# Audio.net
KiCad netlist of a schematic drawn in Altium Designer
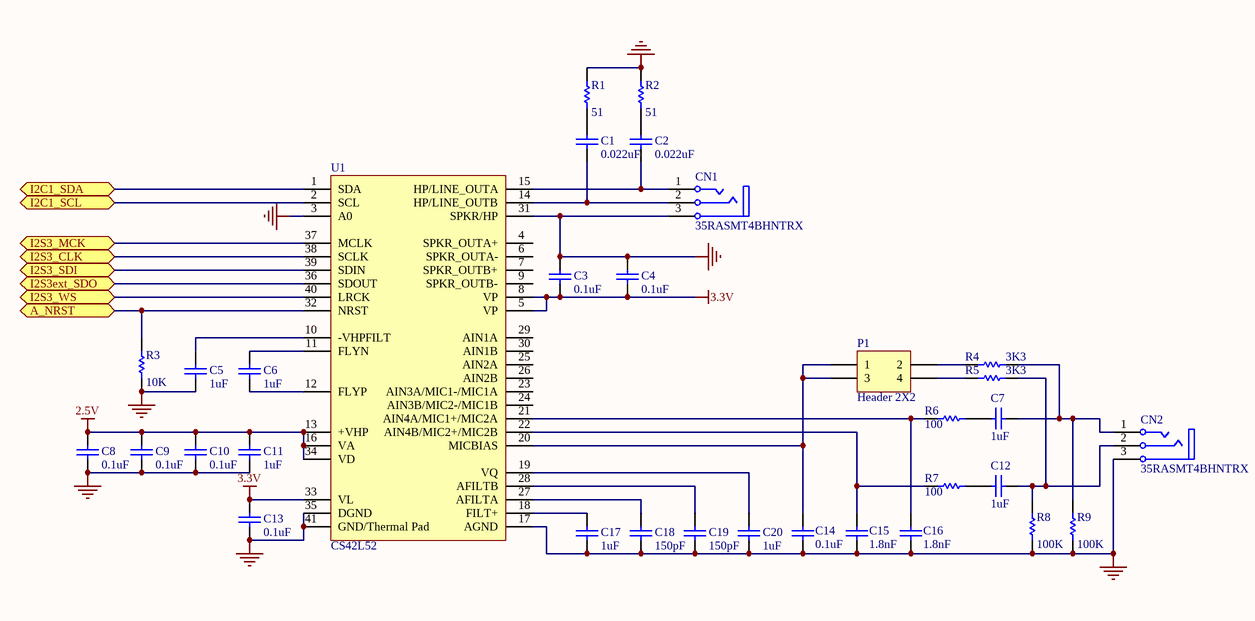
[diagram p0: Audio.SchDoc]

(export (version "E")
  (design (tool "Eeschema 10.0.6"))
  (components
    (comp (ref "C1")
      (value "0.022uF")
      (footprint "CAPC2012N")
      (description "Capacitor")
      (fields (field (name "Comment") "Cap"))
      (libsource (lib "Core429IBaseBoard") (part "Cap"))
    )
    (comp (ref "C2")
      (value "0.022uF")
      (footprint "CAPC2012N")
      (description "Capacitor")
      (fields (field (name "Comment") "Cap"))
      (libsource (lib "Core429IBaseBoard") (part "Cap"))
    )
    (comp (ref "C3")
      (value "0.1uF")
      (footprint "CAPC2012N")
      (description "Capacitor")
      (fields (field (name "Comment") "Cap"))
      (libsource (lib "Core429IBaseBoard") (part "Cap"))
    )
    (comp (ref "C4")
      (value "0.1uF")
      (footprint "CAPC2012N")
      (description "Capacitor")
      (fields (field (name "Comment") "Cap"))
      (libsource (lib "Core429IBaseBoard") (part "Cap"))
    )
    (comp (ref "C5")
      (value "1uF")
      (footprint "CAPC3216N")
      (description "Capacitor")
      (fields (field (name "Comment") "Cap"))
      (libsource (lib "Core429IBaseBoard") (part "Cap"))
    )
    (comp (ref "C6")
      (value "1uF")
      (footprint "CAPC3216N")
      (description "Capacitor")
      (fields (field (name "Comment") "Cap"))
      (libsource (lib "Core429IBaseBoard") (part "Cap"))
    )
    (comp (ref "C7")
      (value "1uF")
      (footprint "CAPC3216N")
      (description "Capacitor")
      (fields (field (name "Comment") "Cap"))
      (libsource (lib "Core429IBaseBoard") (part "Cap"))
    )
    (comp (ref "C8")
      (value "0.1uF")
      (footprint "CAPC2012N")
      (description "Capacitor")
      (fields (field (name "Comment") "Cap"))
      (libsource (lib "Core429IBaseBoard") (part "Cap"))
    )
    (comp (ref "C9")
      (value "0.1uF")
      (footprint "CAPC2012N")
      (description "Capacitor")
      (fields (field (name "Comment") "Cap"))
      (libsource (lib "Core429IBaseBoard") (part "Cap"))
    )
    (comp (ref "C10")
      (value "0.1uF")
      (footprint "CAPC2012N")
      (description "Capacitor")
      (fields (field (name "Comment") "Cap"))
      (libsource (lib "Core429IBaseBoard") (part "Cap"))
    )
    (comp (ref "C11")
      (value "1uF")
      (footprint "CAPC3216N")
      (description "Capacitor")
      (fields (field (name "Comment") "Cap"))
      (libsource (lib "Core429IBaseBoard") (part "Cap"))
    )
    (comp (ref "C12")
      (value "1uF")
      (footprint "CAPC3216N")
      (description "Capacitor")
      (fields (field (name "Comment") "Cap"))
      (libsource (lib "Core429IBaseBoard") (part "Cap"))
    )
    (comp (ref "C13")
      (value "0.1uF")
      (footprint "CAPC2012N")
      (description "Capacitor")
      (fields (field (name "Comment") "Cap"))
      (libsource (lib "Core429IBaseBoard") (part "Cap"))
    )
    (comp (ref "C14")
      (value "0.1uF")
      (footprint "CAPC2012N")
      (description "Capacitor")
      (fields (field (name "Comment") "Cap"))
      (libsource (lib "Core429IBaseBoard") (part "Cap"))
    )
    (comp (ref "C15")
      (value "1.8nF")
      (footprint "CAPC2012N")
      (description "Capacitor")
      (fields (field (name "Comment") "Cap"))
      (libsource (lib "Core429IBaseBoard") (part "Cap"))
    )
    (comp (ref "C16")
      (value "1.8nF")
      (footprint "CAPC2012N")
      (description "Capacitor")
      (fields (field (name "Comment") "Cap"))
      (libsource (lib "Core429IBaseBoard") (part "Cap"))
    )
    (comp (ref "C17")
      (value "1uF")
      (footprint "CAPC3216N")
      (description "Capacitor")
      (fields (field (name "Comment") "Cap"))
      (libsource (lib "Core429IBaseBoard") (part "Cap"))
    )
    (comp (ref "C18")
      (value "150pF")
      (footprint "CAPC2012N")
      (description "Capacitor")
      (fields (field (name "Comment") "Cap"))
      (libsource (lib "Core429IBaseBoard") (part "Cap"))
    )
    (comp (ref "C19")
      (value "150pF")
      (footprint "CAPC2012N")
      (description "Capacitor")
      (fields (field (name "Comment") "Cap"))
      (libsource (lib "Core429IBaseBoard") (part "Cap"))
    )
    (comp (ref "C20")
      (value "1uF")
      (footprint "CAPC3216N")
      (description "Capacitor")
      (fields (field (name "Comment") "Cap"))
      (libsource (lib "Core429IBaseBoard") (part "Cap"))
    )
    (comp (ref "CN1")
      (value "35RASMT4BHNTRX")
      (footprint "35RASMT4BHNTRX")
      (description "3.5mm Stereo Jack")
      (libsource (lib "Core429IBaseBoardVerE") (part "Phonejack3"))
    )
    (comp (ref "CN2")
      (value "35RASMT4BHNTRX")
      (footprint "35RASMT4BHNTRX")
      (description "3.5mm Stereo Jack")
      (libsource (lib "Core429IBaseBoardVerE") (part "Phonejack3"))
    )
    (comp (ref "P1")
      (value "Header 2X2")
      (footprint "HDR2X2")
      (description "Header, 2-Pin, Dual row")
      (libsource (lib "Core429IBaseBoardVerE") (part "Header 2X2"))
    )
    (comp (ref "R1")
      (value "51")
      (footprint "RESC2012N")
      (description "Resistor")
      (fields (field (name "Comment") "1206"))
      (libsource (lib "Core429IBaseBoard") (part "Res"))
    )
    (comp (ref "R2")
      (value "51")
      (footprint "RESC2012N")
      (description "Resistor")
      (fields (field (name "Comment") "1206"))
      (libsource (lib "Core429IBaseBoard") (part "Res"))
    )
    (comp (ref "R3")
      (value "10K")
      (footprint "RESC2012N")
      (description "Resistor")
      (fields (field (name "Comment") "1206"))
      (libsource (lib "Core429IBaseBoard") (part "Res"))
    )
    (comp (ref "R4")
      (value "3K3")
      (footprint "RESC2012N")
      (description "Resistor")
      (fields (field (name "Comment") "1206"))
      (libsource (lib "Core429IBaseBoard") (part "Res"))
    )
    (comp (ref "R5")
      (value "3K3")
      (footprint "RESC2012N")
      (description "Resistor")
      (fields (field (name "Comment") "1206"))
      (libsource (lib "Core429IBaseBoard") (part "Res"))
    )
    (comp (ref "R6")
      (value "100")
      (footprint "RESC2012N")
      (description "Resistor")
      (fields (field (name "Comment") "1206"))
      (libsource (lib "Core429IBaseBoard") (part "Res"))
    )
    (comp (ref "R7")
      (value "100")
      (footprint "RESC2012N")
      (description "Resistor")
      (fields (field (name "Comment") "1206"))
      (libsource (lib "Core429IBaseBoard") (part "Res"))
    )
    (comp (ref "R8")
      (value "100K")
      (footprint "RESC2012N")
      (description "Resistor")
      (fields (field (name "Comment") "1206"))
      (libsource (lib "Core429IBaseBoard") (part "Res"))
    )
    (comp (ref "R9")
      (value "100K")
      (footprint "RESC2012N")
      (description "Resistor")
      (fields (field (name "Comment") "1206"))
      (libsource (lib "Core429IBaseBoard") (part "Res"))
    )
    (comp (ref "U1")
      (value "CS42L52")
      (footprint "QFN50P600X600X100-40M")
      (description "Low-power, Stereo CODEC w/ Headphone & Speaker Amps")
      (libsource (lib "Core429IBaseBoardVerE") (part "CS42L52"))
    )
  )
  (nets
    (net (code "1") (name "/A_NRST") (class "Default")
      (node (ref "R3") (pin "2") (pinfunction "2_2") (pintype "passive"))
      (node (ref "U1") (pin "32") (pinfunction "NRST_32") (pintype "passive"))
    )
    (net (code "2") (name "/I2C1_SCL") (class "Default")
      (node (ref "U1") (pin "2") (pinfunction "SCL_2") (pintype "passive"))
    )
    (net (code "3") (name "/I2C1_SDA") (class "Default")
      (node (ref "U1") (pin "1") (pinfunction "SDA_1") (pintype "passive"))
    )
    (net (code "4") (name "/I2S3_CLK") (class "Default")
      (node (ref "U1") (pin "38") (pinfunction "SCLK_38") (pintype "passive"))
    )
    (net (code "5") (name "/I2S3_MCK") (class "Default")
      (node (ref "U1") (pin "37") (pinfunction "MCLK_37") (pintype "passive"))
    )
    (net (code "6") (name "/I2S3_SDI") (class "Default")
      (node (ref "U1") (pin "39") (pinfunction "SDIN_39") (pintype "passive"))
    )
    (net (code "7") (name "/I2S3_WS") (class "Default")
      (node (ref "U1") (pin "40") (pinfunction "LRCK_40") (pintype "passive"))
    )
    (net (code "8") (name "/I2S3ext_SDO") (class "Default")
      (node (ref "U1") (pin "36") (pinfunction "SDOUT_36") (pintype "passive"))
    )
    (net (code "9") (name "2.5V") (class "Default")
      (node (ref "C10") (pin "2") (pinfunction "2_2") (pintype "passive"))
      (node (ref "C11") (pin "2") (pinfunction "2_2") (pintype "passive"))
      (node (ref "C8") (pin "2") (pinfunction "2_2") (pintype "passive"))
      (node (ref "C9") (pin "2") (pinfunction "2_2") (pintype "passive"))
      (node (ref "U1") (pin "13") (pinfunction "+VHP_13") (pintype "passive"))
      (node (ref "U1") (pin "16") (pinfunction "VA_16") (pintype "passive"))
      (node (ref "U1") (pin "34") (pinfunction "VD_34") (pintype "passive"))
    )
    (net (code "10") (name "3.3V") (class "Default")
      (node (ref "C13") (pin "2") (pinfunction "2_2") (pintype "passive"))
      (node (ref "C3") (pin "1") (pinfunction "1_1") (pintype "passive"))
      (node (ref "C4") (pin "1") (pinfunction "1_1") (pintype "passive"))
      (node (ref "U1") (pin "33") (pinfunction "VL_33") (pintype "passive"))
      (node (ref "U1") (pin "5") (pinfunction "VP_5") (pintype "passive"))
      (node (ref "U1") (pin "8") (pinfunction "VP_8") (pintype "passive"))
    )
    (net (code "11") (name "DGND") (class "Default")
      (node (ref "C10") (pin "1") (pinfunction "1_1") (pintype "passive"))
      (node (ref "C11") (pin "1") (pinfunction "1_1") (pintype "passive"))
      (node (ref "C13") (pin "1") (pinfunction "1_1") (pintype "passive"))
      (node (ref "C14") (pin "2") (pinfunction "2_2") (pintype "passive"))
      (node (ref "C15") (pin "2") (pinfunction "2_2") (pintype "passive"))
      (node (ref "C16") (pin "2") (pinfunction "2_2") (pintype "passive"))
      (node (ref "C17") (pin "1") (pinfunction "1_1") (pintype "passive"))
      (node (ref "C18") (pin "1") (pinfunction "1_1") (pintype "passive"))
      (node (ref "C19") (pin "1") (pinfunction "1_1") (pintype "passive"))
      (node (ref "C20") (pin "1") (pinfunction "1_1") (pintype "passive"))
      (node (ref "C3") (pin "2") (pinfunction "2_2") (pintype "passive"))
      (node (ref "C4") (pin "2") (pinfunction "2_2") (pintype "passive"))
      (node (ref "C5") (pin "1") (pinfunction "1_1") (pintype "passive"))
      (node (ref "C8") (pin "1") (pinfunction "1_1") (pintype "passive"))
      (node (ref "C9") (pin "1") (pinfunction "1_1") (pintype "passive"))
      (node (ref "CN1") (pin "3") (pinfunction "S_3") (pintype "passive"))
      (node (ref "CN2") (pin "3") (pinfunction "S_3") (pintype "passive"))
      (node (ref "R1") (pin "2") (pinfunction "2_2") (pintype "passive"))
      (node (ref "R2") (pin "2") (pinfunction "2_2") (pintype "passive"))
      (node (ref "R3") (pin "1") (pinfunction "1_1") (pintype "passive"))
      (node (ref "R8") (pin "1") (pinfunction "1_1") (pintype "passive"))
      (node (ref "R9") (pin "1") (pinfunction "1_1") (pintype "passive"))
      (node (ref "U1") (pin "17") (pinfunction "AGND_17") (pintype "passive"))
      (node (ref "U1") (pin "3") (pinfunction "A0_3") (pintype "passive"))
      (node (ref "U1") (pin "31") (pinfunction "SPKR/HP_31") (pintype "passive"))
      (node (ref "U1") (pin "35") (pinfunction "DGND_35") (pintype "passive"))
      (node (ref "U1") (pin "41") (pinfunction "GND/Thermal_Pad_41") (pintype "passive"))
    )
    (net (code "12") (name "Net-(C1-Pad2)") (class "Default")
      (node (ref "C1") (pin "2") (pinfunction "2_2") (pintype "passive"))
      (node (ref "R1") (pin "1") (pinfunction "1_1") (pintype "passive"))
    )
    (net (code "13") (name "Net-(C2-Pad2)") (class "Default")
      (node (ref "C2") (pin "2") (pinfunction "2_2") (pintype "passive"))
      (node (ref "R2") (pin "1") (pinfunction "1_1") (pintype "passive"))
    )
    (net (code "14") (name "Net-(C7-Pad2)") (class "Default")
      (node (ref "C7") (pin "2") (pinfunction "2_2") (pintype "passive"))
      (node (ref "R6") (pin "1") (pinfunction "1_1") (pintype "passive"))
    )
    (net (code "15") (name "Net-(C12-Pad2)") (class "Default")
      (node (ref "C12") (pin "2") (pinfunction "2_2") (pintype "passive"))
      (node (ref "R7") (pin "1") (pinfunction "1_1") (pintype "passive"))
    )
    (net (code "16") (name "Net-(CN1-R)") (class "Default")
      (node (ref "C1") (pin "1") (pinfunction "1_1") (pintype "passive"))
      (node (ref "CN1") (pin "2") (pinfunction "R_2") (pintype "passive"))
      (node (ref "U1") (pin "14") (pinfunction "HP/LINE_OUTB_14") (pintype "passive"))
    )
    (net (code "17") (name "Net-(CN1-T)") (class "Default")
      (node (ref "C2") (pin "1") (pinfunction "1_1") (pintype "passive"))
      (node (ref "CN1") (pin "1") (pinfunction "T_1") (pintype "passive"))
      (node (ref "U1") (pin "15") (pinfunction "HP/LINE_OUTA_15") (pintype "passive"))
    )
    (net (code "18") (name "Net-(CN2-R)") (class "Default")
      (node (ref "C12") (pin "1") (pinfunction "1_1") (pintype "passive"))
      (node (ref "CN2") (pin "2") (pinfunction "R_2") (pintype "passive"))
      (node (ref "R5") (pin "1") (pinfunction "1_1") (pintype "passive"))
      (node (ref "R8") (pin "2") (pinfunction "2_2") (pintype "passive"))
    )
    (net (code "19") (name "Net-(CN2-T)") (class "Default")
      (node (ref "C7") (pin "1") (pinfunction "1_1") (pintype "passive"))
      (node (ref "CN2") (pin "1") (pinfunction "T_1") (pintype "passive"))
      (node (ref "R4") (pin "1") (pinfunction "1_1") (pintype "passive"))
      (node (ref "R9") (pin "2") (pinfunction "2_2") (pintype "passive"))
    )
    (net (code "20") (name "Net-(P1-Pad2)") (class "Default")
      (node (ref "P1") (pin "2") (pinfunction "2_2") (pintype "passive"))
      (node (ref "R4") (pin "2") (pinfunction "2_2") (pintype "passive"))
    )
    (net (code "21") (name "Net-(P1-Pad4)") (class "Default")
      (node (ref "P1") (pin "4") (pinfunction "4_4") (pintype "passive"))
      (node (ref "R5") (pin "2") (pinfunction "2_2") (pintype "passive"))
    )
    (net (code "22") (name "Net-(U1--VHPFILT)") (class "Default")
      (node (ref "C5") (pin "2") (pinfunction "2_2") (pintype "passive"))
      (node (ref "U1") (pin "10") (pinfunction "-VHPFILT_10") (pintype "passive"))
    )
    (net (code "23") (name "Net-(U1-AFILTA)") (class "Default")
      (node (ref "C18") (pin "2") (pinfunction "2_2") (pintype "passive"))
      (node (ref "U1") (pin "27") (pinfunction "AFILTA_27") (pintype "passive"))
    )
    (net (code "24") (name "Net-(U1-AFILTB)") (class "Default")
      (node (ref "C19") (pin "2") (pinfunction "2_2") (pintype "passive"))
      (node (ref "U1") (pin "28") (pinfunction "AFILTB_28") (pintype "passive"))
    )
    (net (code "25") (name "Net-(U1-AIN4A{slash}MIC1+{slash}MIC2A)") (class "Default")
      (node (ref "C16") (pin "1") (pinfunction "1_1") (pintype "passive"))
      (node (ref "R6") (pin "2") (pinfunction "2_2") (pintype "passive"))
      (node (ref "U1") (pin "21") (pinfunction "AIN4A/MIC1+/MIC2A_21") (pintype "passive"))
    )
    (net (code "26") (name "Net-(U1-AIN4B{slash}MIC2+{slash}MIC2B)") (class "Default")
      (node (ref "C15") (pin "1") (pinfunction "1_1") (pintype "passive"))
      (node (ref "R7") (pin "2") (pinfunction "2_2") (pintype "passive"))
      (node (ref "U1") (pin "22") (pinfunction "AIN4B/MIC2+/MIC2B_22") (pintype "passive"))
    )
    (net (code "27") (name "Net-(U1-FILT+)") (class "Default")
      (node (ref "C17") (pin "2") (pinfunction "2_2") (pintype "passive"))
      (node (ref "U1") (pin "18") (pinfunction "FILT+_18") (pintype "passive"))
    )
    (net (code "28") (name "Net-(U1-FLYN)") (class "Default")
      (node (ref "C6") (pin "2") (pinfunction "2_2") (pintype "passive"))
      (node (ref "U1") (pin "11") (pinfunction "FLYN_11") (pintype "passive"))
    )
    (net (code "29") (name "Net-(U1-FLYP)") (class "Default")
      (node (ref "C6") (pin "1") (pinfunction "1_1") (pintype "passive"))
      (node (ref "U1") (pin "12") (pinfunction "FLYP_12") (pintype "passive"))
    )
    (net (code "30") (name "Net-(U1-MICBIAS)") (class "Default")
      (node (ref "C14") (pin "1") (pinfunction "1_1") (pintype "passive"))
      (node (ref "P1") (pin "1") (pinfunction "1_1") (pintype "passive"))
      (node (ref "P1") (pin "3") (pinfunction "3_3") (pintype "passive"))
      (node (ref "U1") (pin "20") (pinfunction "MICBIAS_20") (pintype "passive"))
    )
    (net (code "31") (name "Net-(U1-VQ)") (class "Default")
      (node (ref "C20") (pin "2") (pinfunction "2_2") (pintype "passive"))
      (node (ref "U1") (pin "19") (pinfunction "VQ_19") (pintype "passive"))
    )
    (net (code "32") (name "unconnected-(U1-AIN1A-Pad29)") (class "Default")
      (node (ref "U1") (pin "29") (pinfunction "AIN1A_29") (pintype "passive"))
    )
    (net (code "33") (name "unconnected-(U1-AIN1B-Pad30)") (class "Default")
      (node (ref "U1") (pin "30") (pinfunction "AIN1B_30") (pintype "passive"))
    )
    (net (code "34") (name "unconnected-(U1-AIN2A-Pad25)") (class "Default")
      (node (ref "U1") (pin "25") (pinfunction "AIN2A_25") (pintype "passive"))
    )
    (net (code "35") (name "unconnected-(U1-AIN2B-Pad26)") (class "Default")
      (node (ref "U1") (pin "26") (pinfunction "AIN2B_26") (pintype "passive"))
    )
    (net (code "36") (name "unconnected-(U1-AIN3A{slash}MIC1-{slash}MIC1A-Pad23)") (class "Default")
      (node (ref "U1") (pin "23") (pinfunction "AIN3A/MIC1-/MIC1A_23") (pintype "passive"))
    )
    (net (code "37") (name "unconnected-(U1-AIN3B{slash}MIC2-{slash}MIC1B-Pad24)") (class "Default")
      (node (ref "U1") (pin "24") (pinfunction "AIN3B/MIC2-/MIC1B_24") (pintype "passive"))
    )
    (net (code "38") (name "unconnected-(U1-SPKR_OUTA+-Pad4)") (class "Default")
      (node (ref "U1") (pin "4") (pinfunction "SPKR_OUTA+_4") (pintype "passive"))
    )
    (net (code "39") (name "unconnected-(U1-SPKR_OUTA--Pad6)") (class "Default")
      (node (ref "U1") (pin "6") (pinfunction "SPKR_OUTA-_6") (pintype "passive"))
    )
    (net (code "40") (name "unconnected-(U1-SPKR_OUTB+-Pad7)") (class "Default")
      (node (ref "U1") (pin "7") (pinfunction "SPKR_OUTB+_7") (pintype "passive"))
    )
    (net (code "41") (name "unconnected-(U1-SPKR_OUTB--Pad9)") (class "Default")
      (node (ref "U1") (pin "9") (pinfunction "SPKR_OUTB-_9") (pintype "passive"))
    )
  )
)
